# PA_classD.net
KiCad netlist of a schematic drawn in Altium Designer
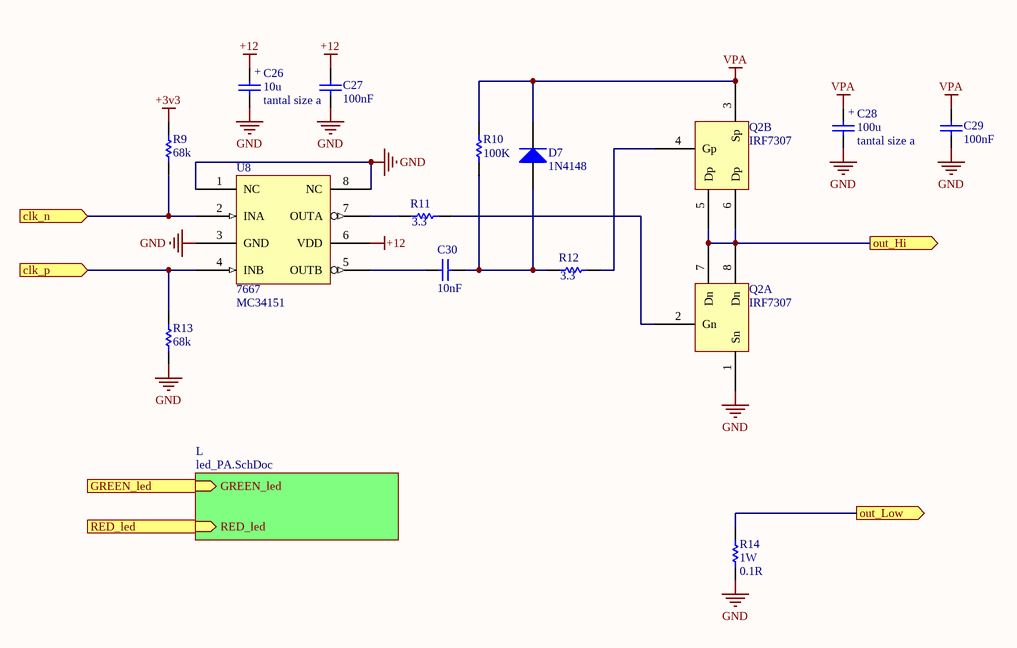
[diagram p0: PA_classD.SchDoc]

(export (version "E")
  (design (tool "Eeschema 10.0.6"))
  (components
    (comp (ref "C26")
      (value "tantal size a")
      (footprint "CAPP 1206 (3216X18L) Size A")
      (fields (field (name "ALTIUM_VALUE") "10u"))
      (libsource (lib "Altium library (www.AVRelec.com)") (part "Cap Pol"))
    )
    (comp (ref "C27")
      (value "100nF")
      (footprint "SMD_CAP_0805")
      (description "CAP-100Nf")
      (libsource (lib "Altium library (www.AVRelec.com)") (part "Cap ceramic"))
    )
    (comp (ref "C28")
      (value "tantal size a")
      (footprint "CAPP 1206 (3216X18L) Size A")
      (fields (field (name "ALTIUM_VALUE") "100u"))
      (libsource (lib "Altium library (www.AVRelec.com)") (part "Cap Pol"))
    )
    (comp (ref "C29")
      (value "100nF")
      (footprint "SMD_CAP_0805")
      (description "CAP-100Nf")
      (libsource (lib "Altium library (www.AVRelec.com)") (part "Cap ceramic"))
    )
    (comp (ref "C30")
      (value "10nF")
      (footprint "SMD_CAP_0805")
      (description "CAP-100Nf")
      (libsource (lib "Altium library (www.AVRelec.com)") (part "Cap ceramic"))
    )
    (comp (ref "D7")
      (value "1N4148")
      (footprint "LL4148")
      (description "High Conductance Fast Diode")
      (fields (field (name "PUBLISHER") "Altium Limited"))
      (libsource (lib "Miscellaneous Devices") (part "Diode 1N4148"))
    )
    (comp (ref "Q2")
      (value "IRF7307")
      (footprint "Miscellaneous Devices:SO8_M")
      (libsource (lib "PA_sch") (part "IRF7106"))
    )
    (comp (ref "R9")
      (value "68k")
      (footprint "RES 0805 (2012X06L)")
      (description "Resistor")
      (fields (field (name "PUBLISHER") "Altium Limited"))
      (libsource (lib "Miscellaneous Devices") (part "Res1"))
    )
    (comp (ref "R10")
      (value "100K")
      (footprint "RES 0805 (2012X06L)")
      (description "Resistor")
      (fields (field (name "PUBLISHER") "Altium Limited"))
      (libsource (lib "Miscellaneous Devices") (part "Res1"))
    )
    (comp (ref "R11")
      (value "3.3")
      (footprint "RES 0805 (2012X06L)")
      (description "Resistor")
      (fields (field (name "PUBLISHER") "Altium Limited"))
      (libsource (lib "Miscellaneous Devices") (part "Res1"))
    )
    (comp (ref "R12")
      (value "3.3")
      (footprint "RES 0805 (2012X06L)")
      (description "Resistor")
      (fields (field (name "PUBLISHER") "Altium Limited"))
      (libsource (lib "Miscellaneous Devices") (part "Res1"))
    )
    (comp (ref "R13")
      (value "68k")
      (footprint "RES 0805 (2012X06L)")
      (description "Resistor")
      (fields (field (name "PUBLISHER") "Altium Limited"))
      (libsource (lib "Miscellaneous Devices") (part "Res1"))
    )
    (comp (ref "R14")
      (value "1W")
      (footprint "Axial 1W  7_0mm")
      (description "Resistor")
      (fields (field (name "ALTIUM_VALUE") "0.1R") (field (name "PUBLISHER") "Altium Limited"))
      (libsource (lib "Miscellaneous Devices") (part "Res1"))
    )
    (comp (ref "U8")
      (value "7667")
      (footprint "Miscellaneous Devices:SO8_M")
      (libsource (lib "PA_sch") (part "ICL7667"))
    )
  )
  (nets
    (net (code "1") (name "+3v3") (class "Default")
      (node (ref "R9") (pin "1") (pinfunction "1_1") (pintype "passive"))
    )
    (net (code "2") (name "+12") (class "Default")
      (node (ref "C26") (pin "+") (pinfunction "+_+") (pintype "passive"))
      (node (ref "C27") (pin "1") (pinfunction "1_1") (pintype "passive"))
      (node (ref "U8") (pin "6") (pinfunction "VDD_6") (pintype "power_in"))
    )
    (net (code "5") (name "/clk_n") (class "Default")
      (node (ref "R9") (pin "2") (pinfunction "2_2") (pintype "passive"))
      (node (ref "U8") (pin "2") (pinfunction "INA_2") (pintype "input"))
    )
    (net (code "6") (name "/clk_p") (class "Default")
      (node (ref "R13") (pin "1") (pinfunction "1_1") (pintype "passive"))
      (node (ref "U8") (pin "4") (pinfunction "INB_4") (pintype "input"))
    )
    (net (code "7") (name "/out_Hi") (class "Default")
      (node (ref "Q2") (pin "5") (pinfunction "Dp_5") (pintype "passive"))
      (node (ref "Q2") (pin "6") (pinfunction "Dp_6") (pintype "passive"))
      (node (ref "Q2") (pin "7") (pinfunction "Dn_7") (pintype "passive"))
      (node (ref "Q2") (pin "8") (pinfunction "Dn_8") (pintype "passive"))
    )
    (net (code "8") (name "/out_Low") (class "Default")
      (node (ref "R14") (pin "2") (pinfunction "2_2") (pintype "passive"))
    )
    (net (code "9") (name "GND") (class "Default")
      (node (ref "C26") (pin "-") (pinfunction "-_-") (pintype "passive"))
      (node (ref "C27") (pin "2") (pinfunction "2_2") (pintype "passive"))
      (node (ref "C28") (pin "-") (pinfunction "-_-") (pintype "passive"))
      (node (ref "C29") (pin "2") (pinfunction "2_2") (pintype "passive"))
      (node (ref "Q2") (pin "1") (pinfunction "Sn_1") (pintype "passive"))
      (node (ref "R13") (pin "2") (pinfunction "2_2") (pintype "passive"))
      (node (ref "R14") (pin "1") (pinfunction "1_1") (pintype "passive"))
      (node (ref "U8") (pin "1") (pinfunction "NC_1") (pintype "passive"))
      (node (ref "U8") (pin "3") (pinfunction "GND_3") (pintype "power_in"))
      (node (ref "U8") (pin "8") (pinfunction "NC_8") (pintype "passive"))
    )
    (net (code "10") (name "Net-(D7-A)") (class "Default")
      (node (ref "C30") (pin "2") (pinfunction "2_2") (pintype "passive"))
      (node (ref "D7") (pin "1") (pinfunction "A_1") (pintype "passive"))
      (node (ref "R10") (pin "2") (pinfunction "2_2") (pintype "passive"))
      (node (ref "R12") (pin "2") (pinfunction "2_2") (pintype "passive"))
    )
    (net (code "11") (name "Net-(Q2A-Gn)") (class "Default")
      (node (ref "Q2") (pin "2") (pinfunction "Gn_2") (pintype "passive"))
      (node (ref "R11") (pin "1") (pinfunction "1_1") (pintype "passive"))
    )
    (net (code "12") (name "Net-(Q2B-Gp)") (class "Default")
      (node (ref "Q2") (pin "4") (pinfunction "Gp_4") (pintype "passive"))
      (node (ref "R12") (pin "1") (pinfunction "1_1") (pintype "passive"))
    )
    (net (code "13") (name "Net-(U8-OUTA)") (class "Default")
      (node (ref "R11") (pin "2") (pinfunction "2_2") (pintype "passive"))
      (node (ref "U8") (pin "7") (pinfunction "OUTA_7") (pintype "output"))
    )
    (net (code "14") (name "Net-(U8-OUTB)") (class "Default")
      (node (ref "C30") (pin "1") (pinfunction "1_1") (pintype "passive"))
      (node (ref "U8") (pin "5") (pinfunction "OUTB_5") (pintype "output"))
    )
    (net (code "15") (name "VPA") (class "Default")
      (node (ref "C28") (pin "+") (pinfunction "+_+") (pintype "passive"))
      (node (ref "C29") (pin "1") (pinfunction "1_1") (pintype "passive"))
      (node (ref "D7") (pin "2") (pinfunction "K_2") (pintype "passive"))
      (node (ref "Q2") (pin "3") (pinfunction "Sp_3") (pintype "passive"))
      (node (ref "R10") (pin "1") (pinfunction "1_1") (pintype "passive"))
    )
  )
)
